# touch.net
KiCad netlist of a schematic drawn in Altium Designer
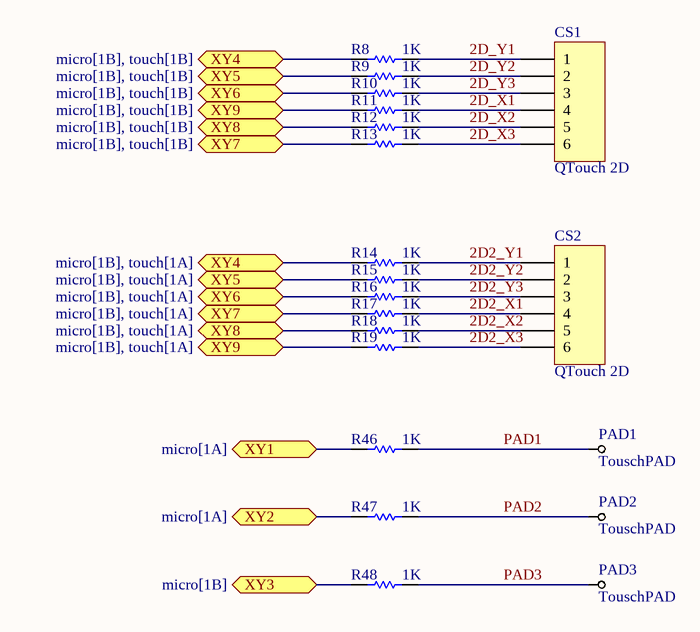
[diagram p0: touch.SchDoc]

(export (version "E")
  (design (tool "Eeschema 10.0.6"))
  (components
    (comp (ref "CS1")
      (value "QTouch 2D")
      (footprint "wheel")
      (description "3 by 3 2D touch surface")
      (fields (field (name "PUBLISHER") "Altium Limited"))
      (libsource (lib "Miscellaneous Connectors") (part "Header 6"))
    )
    (comp (ref "CS2")
      (value "QTouch 2D")
      (footprint "2D_touch _wheel")
      (description "3 by 3 2D touch surface")
      (fields (field (name "PUBLISHER") "Altium Limited"))
      (libsource (lib "Miscellaneous Connectors") (part "Header 6"))
    )
    (comp (ref "PAD1")
      (value "TouschPAD")
      (footprint "touchpad7")
      (libsource (lib "Altium (2)") (part "Test Point"))
    )
    (comp (ref "PAD2")
      (value "TouschPAD")
      (footprint "touchpad7")
      (libsource (lib "Altium (2)") (part "Test Point"))
    )
    (comp (ref "PAD3")
      (value "TouschPAD")
      (footprint "touchpad7")
      (libsource (lib "Altium (2)") (part "Test Point"))
    )
    (comp (ref "R8")
      (value "1K")
      (footprint "RES 0805 (2012X06L)")
      (description "Resistor")
      (fields (field (name "PUBLISHER") "Altium Limited"))
      (libsource (lib "Miscellaneous Devices") (part "Res1"))
    )
    (comp (ref "R9")
      (value "1K")
      (footprint "RES 0805 (2012X06L)")
      (description "Resistor")
      (fields (field (name "PUBLISHER") "Altium Limited"))
      (libsource (lib "Miscellaneous Devices") (part "Res1"))
    )
    (comp (ref "R10")
      (value "1K")
      (footprint "RES 0805 (2012X06L)")
      (description "Resistor")
      (fields (field (name "PUBLISHER") "Altium Limited"))
      (libsource (lib "Miscellaneous Devices") (part "Res1"))
    )
    (comp (ref "R11")
      (value "1K")
      (footprint "RES 0805 (2012X06L)")
      (description "Resistor")
      (fields (field (name "PUBLISHER") "Altium Limited"))
      (libsource (lib "Miscellaneous Devices") (part "Res1"))
    )
    (comp (ref "R12")
      (value "1K")
      (footprint "RES 0805 (2012X06L)")
      (description "Resistor")
      (fields (field (name "PUBLISHER") "Altium Limited"))
      (libsource (lib "Miscellaneous Devices") (part "Res1"))
    )
    (comp (ref "R13")
      (value "1K")
      (footprint "RES 0805 (2012X06L)")
      (description "Resistor")
      (fields (field (name "PUBLISHER") "Altium Limited"))
      (libsource (lib "Miscellaneous Devices") (part "Res1"))
    )
    (comp (ref "R14")
      (value "1K")
      (footprint "RES 0805 (2012X06L)")
      (description "Resistor")
      (fields (field (name "PUBLISHER") "Altium Limited"))
      (libsource (lib "Miscellaneous Devices") (part "Res1"))
    )
    (comp (ref "R15")
      (value "1K")
      (footprint "RES 0805 (2012X06L)")
      (description "Resistor")
      (fields (field (name "PUBLISHER") "Altium Limited"))
      (libsource (lib "Miscellaneous Devices") (part "Res1"))
    )
    (comp (ref "R16")
      (value "1K")
      (footprint "RES 0805 (2012X06L)")
      (description "Resistor")
      (fields (field (name "PUBLISHER") "Altium Limited"))
      (libsource (lib "Miscellaneous Devices") (part "Res1"))
    )
    (comp (ref "R17")
      (value "1K")
      (footprint "RES 0805 (2012X06L)")
      (description "Resistor")
      (fields (field (name "PUBLISHER") "Altium Limited"))
      (libsource (lib "Miscellaneous Devices") (part "Res1"))
    )
    (comp (ref "R18")
      (value "1K")
      (footprint "RES 0805 (2012X06L)")
      (description "Resistor")
      (fields (field (name "PUBLISHER") "Altium Limited"))
      (libsource (lib "Miscellaneous Devices") (part "Res1"))
    )
    (comp (ref "R19")
      (value "1K")
      (footprint "RES 0805 (2012X06L)")
      (description "Resistor")
      (fields (field (name "PUBLISHER") "Altium Limited"))
      (libsource (lib "Miscellaneous Devices") (part "Res1"))
    )
    (comp (ref "R46")
      (value "1K")
      (footprint "RES 0805 (2012X06L)")
      (description "Resistor")
      (fields (field (name "PUBLISHER") "Altium Limited"))
      (libsource (lib "Miscellaneous Devices") (part "Res1"))
    )
    (comp (ref "R47")
      (value "1K")
      (footprint "RES 0805 (2012X06L)")
      (description "Resistor")
      (fields (field (name "PUBLISHER") "Altium Limited"))
      (libsource (lib "Miscellaneous Devices") (part "Res1"))
    )
    (comp (ref "R48")
      (value "1K")
      (footprint "RES 0805 (2012X06L)")
      (description "Resistor")
      (fields (field (name "PUBLISHER") "Altium Limited"))
      (libsource (lib "Miscellaneous Devices") (part "Res1"))
    )
  )
  (nets
    (net (code "1") (name "/2D2_X1") (class "Default")
      (node (ref "CS2") (pin "4") (pinfunction "4_4") (pintype "passive"))
      (node (ref "R17") (pin "1") (pinfunction "1_1") (pintype "passive"))
    )
    (net (code "2") (name "/2D2_X2") (class "Default")
      (node (ref "CS2") (pin "5") (pinfunction "5_5") (pintype "passive"))
      (node (ref "R18") (pin "1") (pinfunction "1_1") (pintype "passive"))
    )
    (net (code "3") (name "/2D2_X3") (class "Default")
      (node (ref "CS2") (pin "6") (pinfunction "6_6") (pintype "passive"))
      (node (ref "R19") (pin "1") (pinfunction "1_1") (pintype "passive"))
    )
    (net (code "4") (name "/2D2_Y1") (class "Default")
      (node (ref "CS2") (pin "1") (pinfunction "1_1") (pintype "passive"))
      (node (ref "R14") (pin "1") (pinfunction "1_1") (pintype "passive"))
    )
    (net (code "5") (name "/2D2_Y2") (class "Default")
      (node (ref "CS2") (pin "2") (pinfunction "2_2") (pintype "passive"))
      (node (ref "R15") (pin "1") (pinfunction "1_1") (pintype "passive"))
    )
    (net (code "6") (name "/2D2_Y3") (class "Default")
      (node (ref "CS2") (pin "3") (pinfunction "3_3") (pintype "passive"))
      (node (ref "R16") (pin "1") (pinfunction "1_1") (pintype "passive"))
    )
    (net (code "7") (name "/2D_X1") (class "Default")
      (node (ref "CS1") (pin "4") (pinfunction "4_4") (pintype "passive"))
      (node (ref "R11") (pin "1") (pinfunction "1_1") (pintype "passive"))
    )
    (net (code "8") (name "/2D_X2") (class "Default")
      (node (ref "CS1") (pin "5") (pinfunction "5_5") (pintype "passive"))
      (node (ref "R12") (pin "1") (pinfunction "1_1") (pintype "passive"))
    )
    (net (code "9") (name "/2D_X3") (class "Default")
      (node (ref "CS1") (pin "6") (pinfunction "6_6") (pintype "passive"))
      (node (ref "R13") (pin "1") (pinfunction "1_1") (pintype "passive"))
    )
    (net (code "10") (name "/2D_Y1") (class "Default")
      (node (ref "CS1") (pin "1") (pinfunction "1_1") (pintype "passive"))
      (node (ref "R8") (pin "1") (pinfunction "1_1") (pintype "passive"))
    )
    (net (code "11") (name "/2D_Y2") (class "Default")
      (node (ref "CS1") (pin "2") (pinfunction "2_2") (pintype "passive"))
      (node (ref "R9") (pin "1") (pinfunction "1_1") (pintype "passive"))
    )
    (net (code "12") (name "/2D_Y3") (class "Default")
      (node (ref "CS1") (pin "3") (pinfunction "3_3") (pintype "passive"))
      (node (ref "R10") (pin "1") (pinfunction "1_1") (pintype "passive"))
    )
    (net (code "13") (name "/PAD1") (class "Default")
      (node (ref "PAD1") (pin "1") (pinfunction "T_1") (pintype "passive"))
      (node (ref "R46") (pin "1") (pinfunction "1_1") (pintype "passive"))
    )
    (net (code "14") (name "/PAD2") (class "Default")
      (node (ref "PAD2") (pin "1") (pinfunction "T_1") (pintype "passive"))
      (node (ref "R47") (pin "1") (pinfunction "1_1") (pintype "passive"))
    )
    (net (code "15") (name "/PAD3") (class "Default")
      (node (ref "PAD3") (pin "1") (pinfunction "T_1") (pintype "passive"))
      (node (ref "R48") (pin "1") (pinfunction "1_1") (pintype "passive"))
    )
    (net (code "16") (name "/XY1") (class "Default")
      (node (ref "R46") (pin "2") (pinfunction "2_2") (pintype "passive"))
    )
    (net (code "17") (name "/XY2") (class "Default")
      (node (ref "R47") (pin "2") (pinfunction "2_2") (pintype "passive"))
    )
    (net (code "18") (name "/XY3") (class "Default")
      (node (ref "R48") (pin "2") (pinfunction "2_2") (pintype "passive"))
    )
    (net (code "19") (name "/XY4") (class "Default")
      (node (ref "R14") (pin "2") (pinfunction "2_2") (pintype "passive"))
      (node (ref "R8") (pin "2") (pinfunction "2_2") (pintype "passive"))
    )
    (net (code "20") (name "/XY5") (class "Default")
      (node (ref "R15") (pin "2") (pinfunction "2_2") (pintype "passive"))
      (node (ref "R9") (pin "2") (pinfunction "2_2") (pintype "passive"))
    )
    (net (code "21") (name "/XY6") (class "Default")
      (node (ref "R10") (pin "2") (pinfunction "2_2") (pintype "passive"))
      (node (ref "R16") (pin "2") (pinfunction "2_2") (pintype "passive"))
    )
    (net (code "22") (name "/XY7") (class "Default")
      (node (ref "R13") (pin "2") (pinfunction "2_2") (pintype "passive"))
      (node (ref "R17") (pin "2") (pinfunction "2_2") (pintype "passive"))
    )
    (net (code "23") (name "/XY8") (class "Default")
      (node (ref "R12") (pin "2") (pinfunction "2_2") (pintype "passive"))
      (node (ref "R18") (pin "2") (pinfunction "2_2") (pintype "passive"))
    )
    (net (code "24") (name "/XY9") (class "Default")
      (node (ref "R11") (pin "2") (pinfunction "2_2") (pintype "passive"))
      (node (ref "R19") (pin "2") (pinfunction "2_2") (pintype "passive"))
    )
  )
)
